# Schematic_Ledtraitim.net
KiCad netlist of a schematic drawn in Altium Designer
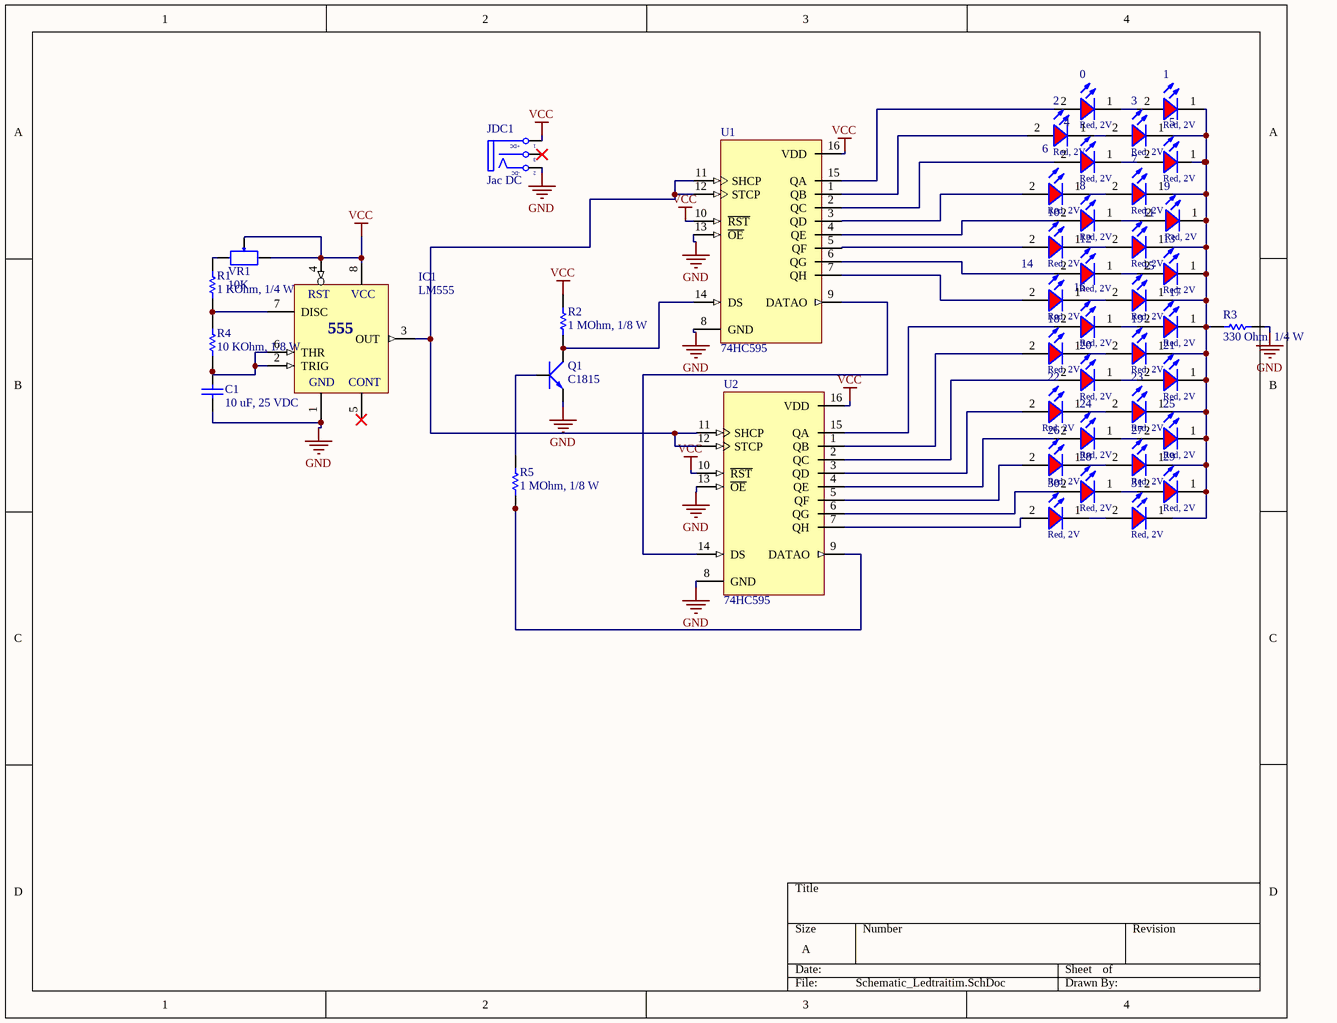
[diagram p0: Schematic_Ledtraitim.SchDoc]

(export (version "E")
  (design (tool "Eeschema 10.0.6"))
  (components
    (comp (ref "0")
      (value "Red, 2V")
      (footprint "WL-SMCW_0805")
      (description "WL-SMCW SMT Mono-color Chip LED Blur, size 0805, Red, 2V, 140deg")
      (libsource (lib "Altium_LED") (part "160805RedBlur"))
    )
    (comp (ref "1")
      (value "Red, 2V")
      (footprint "WL-SMCW_0805")
      (description "WL-SMCW SMT Mono-color Chip LED Blur, size 0805, Red, 2V, 140deg")
      (libsource (lib "Altium_LED") (part "160805RedBlur"))
    )
    (comp (ref "2")
      (value "Red, 2V")
      (footprint "WL-SMCW_0805")
      (description "WL-SMCW SMT Mono-color Chip LED Blur, size 0805, Red, 2V, 140deg")
      (libsource (lib "Altium_LED") (part "160805RedBlur"))
    )
    (comp (ref "3")
      (value "Red, 2V")
      (footprint "WL-SMCW_0805")
      (description "WL-SMCW SMT Mono-color Chip LED Blur, size 0805, Red, 2V, 140deg")
      (libsource (lib "Altium_LED") (part "160805RedBlur"))
    )
    (comp (ref "4")
      (value "Red, 2V")
      (footprint "WL-SMCW_0805")
      (description "WL-SMCW SMT Mono-color Chip LED Blur, size 0805, Red, 2V, 140deg")
      (libsource (lib "Altium_LED") (part "160805RedBlur"))
    )
    (comp (ref "5")
      (value "Red, 2V")
      (footprint "WL-SMCW_0805")
      (description "WL-SMCW SMT Mono-color Chip LED Blur, size 0805, Red, 2V, 140deg")
      (libsource (lib "Altium_LED") (part "160805RedBlur"))
    )
    (comp (ref "6")
      (value "Red, 2V")
      (footprint "WL-SMCW_0805")
      (description "WL-SMCW SMT Mono-color Chip LED Blur, size 0805, Red, 2V, 140deg")
      (libsource (lib "Altium_LED") (part "160805RedBlur"))
    )
    (comp (ref "7")
      (value "Red, 2V")
      (footprint "WL-SMCW_0805")
      (description "WL-SMCW SMT Mono-color Chip LED Blur, size 0805, Red, 2V, 140deg")
      (libsource (lib "Altium_LED") (part "160805RedBlur"))
    )
    (comp (ref "8")
      (value "Red, 2V")
      (footprint "WL-SMCW_0805")
      (description "WL-SMCW SMT Mono-color Chip LED Blur, size 0805, Red, 2V, 140deg")
      (libsource (lib "Altium_LED") (part "160805RedBlur"))
    )
    (comp (ref "9")
      (value "Red, 2V")
      (footprint "WL-SMCW_0805")
      (description "WL-SMCW SMT Mono-color Chip LED Blur, size 0805, Red, 2V, 140deg")
      (libsource (lib "Altium_LED") (part "160805RedBlur"))
    )
    (comp (ref "10")
      (value "Red, 2V")
      (footprint "WL-SMCW_0805")
      (description "WL-SMCW SMT Mono-color Chip LED Blur, size 0805, Red, 2V, 140deg")
      (libsource (lib "Altium_LED") (part "160805RedBlur"))
    )
    (comp (ref "11")
      (value "Red, 2V")
      (footprint "WL-SMCW_0805")
      (description "WL-SMCW SMT Mono-color Chip LED Blur, size 0805, Red, 2V, 140deg")
      (libsource (lib "Altium_LED") (part "160805RedBlur"))
    )
    (comp (ref "12")
      (value "Red, 2V")
      (footprint "WL-SMCW_0805")
      (description "WL-SMCW SMT Mono-color Chip LED Blur, size 0805, Red, 2V, 140deg")
      (libsource (lib "Altium_LED") (part "160805RedBlur"))
    )
    (comp (ref "13")
      (value "Red, 2V")
      (footprint "WL-SMCW_0805")
      (description "WL-SMCW SMT Mono-color Chip LED Blur, size 0805, Red, 2V, 140deg")
      (libsource (lib "Altium_LED") (part "160805RedBlur"))
    )
    (comp (ref "14")
      (value "Red, 2V")
      (footprint "WL-SMCW_0805")
      (description "WL-SMCW SMT Mono-color Chip LED Blur, size 0805, Red, 2V, 140deg")
      (libsource (lib "Altium_LED") (part "160805RedBlur"))
    )
    (comp (ref "15")
      (value "Red, 2V")
      (footprint "WL-SMCW_0805")
      (description "WL-SMCW SMT Mono-color Chip LED Blur, size 0805, Red, 2V, 140deg")
      (libsource (lib "Altium_LED") (part "160805RedBlur"))
    )
    (comp (ref "16")
      (value "Red, 2V")
      (footprint "WL-SMCW_0805")
      (description "WL-SMCW SMT Mono-color Chip LED Blur, size 0805, Red, 2V, 140deg")
      (libsource (lib "Altium_LED") (part "160805RedBlur"))
    )
    (comp (ref "17")
      (value "Red, 2V")
      (footprint "WL-SMCW_0805")
      (description "WL-SMCW SMT Mono-color Chip LED Blur, size 0805, Red, 2V, 140deg")
      (libsource (lib "Altium_LED") (part "160805RedBlur"))
    )
    (comp (ref "18")
      (value "Red, 2V")
      (footprint "WL-SMCW_0805")
      (description "WL-SMCW SMT Mono-color Chip LED Blur, size 0805, Red, 2V, 140deg")
      (libsource (lib "Altium_LED") (part "160805RedBlur"))
    )
    (comp (ref "19")
      (value "Red, 2V")
      (footprint "WL-SMCW_0805")
      (description "WL-SMCW SMT Mono-color Chip LED Blur, size 0805, Red, 2V, 140deg")
      (libsource (lib "Altium_LED") (part "160805RedBlur"))
    )
    (comp (ref "20")
      (value "Red, 2V")
      (footprint "WL-SMCW_0805")
      (description "WL-SMCW SMT Mono-color Chip LED Blur, size 0805, Red, 2V, 140deg")
      (libsource (lib "Altium_LED") (part "160805RedBlur"))
    )
    (comp (ref "21")
      (value "Red, 2V")
      (footprint "WL-SMCW_0805")
      (description "WL-SMCW SMT Mono-color Chip LED Blur, size 0805, Red, 2V, 140deg")
      (libsource (lib "Altium_LED") (part "160805RedBlur"))
    )
    (comp (ref "22")
      (value "Red, 2V")
      (footprint "WL-SMCW_0805")
      (description "WL-SMCW SMT Mono-color Chip LED Blur, size 0805, Red, 2V, 140deg")
      (libsource (lib "Altium_LED") (part "160805RedBlur"))
    )
    (comp (ref "23")
      (value "Red, 2V")
      (footprint "WL-SMCW_0805")
      (description "WL-SMCW SMT Mono-color Chip LED Blur, size 0805, Red, 2V, 140deg")
      (libsource (lib "Altium_LED") (part "160805RedBlur"))
    )
    (comp (ref "24")
      (value "Red, 2V")
      (footprint "WL-SMCW_0805")
      (description "WL-SMCW SMT Mono-color Chip LED Blur, size 0805, Red, 2V, 140deg")
      (libsource (lib "Altium_LED") (part "160805RedBlur"))
    )
    (comp (ref "25")
      (value "Red, 2V")
      (footprint "WL-SMCW_0805")
      (description "WL-SMCW SMT Mono-color Chip LED Blur, size 0805, Red, 2V, 140deg")
      (libsource (lib "Altium_LED") (part "160805RedBlur"))
    )
    (comp (ref "26")
      (value "Red, 2V")
      (footprint "WL-SMCW_0805")
      (description "WL-SMCW SMT Mono-color Chip LED Blur, size 0805, Red, 2V, 140deg")
      (libsource (lib "Altium_LED") (part "160805RedBlur"))
    )
    (comp (ref "27")
      (value "Red, 2V")
      (footprint "WL-SMCW_0805")
      (description "WL-SMCW SMT Mono-color Chip LED Blur, size 0805, Red, 2V, 140deg")
      (libsource (lib "Altium_LED") (part "160805RedBlur"))
    )
    (comp (ref "28")
      (value "Red, 2V")
      (footprint "WL-SMCW_0805")
      (description "WL-SMCW SMT Mono-color Chip LED Blur, size 0805, Red, 2V, 140deg")
      (libsource (lib "Altium_LED") (part "160805RedBlur"))
    )
    (comp (ref "29")
      (value "Red, 2V")
      (footprint "WL-SMCW_0805")
      (description "WL-SMCW SMT Mono-color Chip LED Blur, size 0805, Red, 2V, 140deg")
      (libsource (lib "Altium_LED") (part "160805RedBlur"))
    )
    (comp (ref "30")
      (value "Red, 2V")
      (footprint "WL-SMCW_0805")
      (description "WL-SMCW SMT Mono-color Chip LED Blur, size 0805, Red, 2V, 140deg")
      (libsource (lib "Altium_LED") (part "160805RedBlur"))
    )
    (comp (ref "31")
      (value "Red, 2V")
      (footprint "WL-SMCW_0805")
      (description "WL-SMCW SMT Mono-color Chip LED Blur, size 0805, Red, 2V, 140deg")
      (libsource (lib "Altium_LED") (part "160805RedBlur"))
    )
    (comp (ref "C1")
      (value "10 uF, 25 VDC")
      (footprint "CAP_0805")
      (description "CAP, size 0805, 10 uF, 25 VDC")
      (fields (field (name "TOLERANCE") "+/-10%"))
      (libsource (lib "Altium_Ceramic_Cap") (part "0108051061025"))
    )
    (comp (ref "IC1")
      (value "LM555")
      (footprint "DIP8")
      (description "Timer Circuits")
      (libsource (lib "Cty1") (part "LM555"))
    )
    (comp (ref "JDC1")
      (value "Jac DC")
      (footprint "DC-IN")
      (description "Jac DC input")
      (libsource (lib "Cty1") (part "DCIN"))
    )
    (comp (ref "Q1")
      (value "C1815")
      (footprint "TO126")
      (description "NPN 600mW, ECB")
      (libsource (lib "Devzone_SCHLib") (part "C1815"))
    )
    (comp (ref "R1")
      (value "1 KOhm, 1/4 W")
      (footprint "resistor_0603")
      (description "RES, size 0603, 1 KOhm, 1/4 W")
      (libsource (lib "Altium_Resistor") (part "0006031021"))
    )
    (comp (ref "R2")
      (value "1 MOhm, 1/8 W")
      (footprint "RESISTOR_0805")
      (description "RES, size 0805, 1 MOhm, 1/8 W")
      (libsource (lib "Altium_Resistor") (part "0008051055"))
    )
    (comp (ref "R3")
      (value "330 Ohm, 1/4 W")
      (footprint "resistor_0603")
      (description "RES, size 0603, 330 Ohm, 1/4 W")
      (libsource (lib "Altium_Resistor") (part "0006033311"))
    )
    (comp (ref "R4")
      (value "10 KOhm, 1/8 W")
      (footprint "RESISTOR_0805")
      (description "RES, size 0805, 10 KOhm, 1/8 W")
      (libsource (lib "Altium_Resistor") (part "0008051035"))
    )
    (comp (ref "R5")
      (value "1 MOhm, 1/8 W")
      (footprint "RESISTOR_0805")
      (description "RES, size 0805, 1 MOhm, 1/8 W")
      (libsource (lib "Altium_Resistor") (part "0008051055"))
    )
    (comp (ref "U1")
      (value "74HC595")
      (footprint "DIP16")
      (description "8-Bit Serial-Input/Serial or Prallel-Output Shift Register with Latched 3-State Outputs")
      (fields (field (name "PUBLISHER") "Altium Limited"))
      (libsource (lib "Cty1") (part "74HC595"))
    )
    (comp (ref "U2")
      (value "74HC595")
      (footprint "DIP16")
      (description "8-Bit Serial-Input/Serial or Prallel-Output Shift Register with Latched 3-State Outputs")
      (fields (field (name "PUBLISHER") "Altium Limited"))
      (libsource (lib "Cty1") (part "74HC595"))
    )
    (comp (ref "VR1")
      (value "10K")
      (footprint "VOL_1")
      (description "Var Resistor")
      (libsource (lib "Cty1") (part "Var Resitor"))
    )
  )
  (nets
    (net (code "2") (name "GND") (class "Default")
      (node (ref "C1") (pin "1") (pinfunction "1_1") (pintype "passive"))
      (node (ref "IC1") (pin "1") (pinfunction "GND_1") (pintype "power_in"))
      (node (ref "JDC1") (pin "2") (pinfunction "TN_2") (pintype "passive"))
      (node (ref "Q1") (pin "3") (pinfunction "E_3") (pintype "passive"))
      (node (ref "R3") (pin "2") (pinfunction "2_2") (pintype "passive"))
      (node (ref "U1") (pin "13") (pinfunction "~{OE}_13") (pintype "input"))
      (node (ref "U1") (pin "8") (pinfunction "GND_8") (pintype "power_in"))
      (node (ref "U2") (pin "13") (pinfunction "~{OE}_13") (pintype "input"))
      (node (ref "U2") (pin "8") (pinfunction "GND_8") (pintype "power_in"))
    )
    (net (code "3") (name "Net-(0-A)") (class "Default")
      (node (ref "0") (pin "2") (pinfunction "A_2") (pintype "passive"))
      (node (ref "U1") (pin "15") (pinfunction "QA_15") (pintype "tri_state"))
    )
    (net (code "4") (name "Net-(0-K)") (class "Default")
      (node (ref "0") (pin "1") (pinfunction "K_1") (pintype "passive"))
      (node (ref "1") (pin "2") (pinfunction "A_2") (pintype "passive"))
    )
    (net (code "5") (name "Net-(1-K)") (class "Default")
      (node (ref "1") (pin "1") (pinfunction "K_1") (pintype "passive"))
      (node (ref "11") (pin "1") (pinfunction "K_1") (pintype "passive"))
      (node (ref "13") (pin "1") (pinfunction "K_1") (pintype "passive"))
      (node (ref "15") (pin "1") (pinfunction "K_1") (pintype "passive"))
      (node (ref "17") (pin "1") (pinfunction "K_1") (pintype "passive"))
      (node (ref "19") (pin "1") (pinfunction "K_1") (pintype "passive"))
      (node (ref "21") (pin "1") (pinfunction "K_1") (pintype "passive"))
      (node (ref "23") (pin "1") (pinfunction "K_1") (pintype "passive"))
      (node (ref "25") (pin "1") (pinfunction "K_1") (pintype "passive"))
      (node (ref "27") (pin "1") (pinfunction "K_1") (pintype "passive"))
      (node (ref "29") (pin "1") (pinfunction "K_1") (pintype "passive"))
      (node (ref "3") (pin "1") (pinfunction "K_1") (pintype "passive"))
      (node (ref "31") (pin "1") (pinfunction "K_1") (pintype "passive"))
      (node (ref "5") (pin "1") (pinfunction "K_1") (pintype "passive"))
      (node (ref "7") (pin "1") (pinfunction "K_1") (pintype "passive"))
      (node (ref "9") (pin "1") (pinfunction "K_1") (pintype "passive"))
      (node (ref "R3") (pin "1") (pinfunction "1_1") (pintype "passive"))
    )
    (net (code "6") (name "Net-(2-A)") (class "Default")
      (node (ref "2") (pin "2") (pinfunction "A_2") (pintype "passive"))
      (node (ref "U1") (pin "1") (pinfunction "QB_1") (pintype "tri_state"))
    )
    (net (code "7") (name "Net-(2-K)") (class "Default")
      (node (ref "2") (pin "1") (pinfunction "K_1") (pintype "passive"))
      (node (ref "3") (pin "2") (pinfunction "A_2") (pintype "passive"))
    )
    (net (code "8") (name "Net-(4-A)") (class "Default")
      (node (ref "4") (pin "2") (pinfunction "A_2") (pintype "passive"))
      (node (ref "U1") (pin "2") (pinfunction "QC_2") (pintype "tri_state"))
    )
    (net (code "9") (name "Net-(4-K)") (class "Default")
      (node (ref "4") (pin "1") (pinfunction "K_1") (pintype "passive"))
      (node (ref "5") (pin "2") (pinfunction "A_2") (pintype "passive"))
    )
    (net (code "10") (name "Net-(6-A)") (class "Default")
      (node (ref "6") (pin "2") (pinfunction "A_2") (pintype "passive"))
      (node (ref "U1") (pin "3") (pinfunction "QD_3") (pintype "tri_state"))
    )
    (net (code "11") (name "Net-(6-K)") (class "Default")
      (node (ref "6") (pin "1") (pinfunction "K_1") (pintype "passive"))
      (node (ref "7") (pin "2") (pinfunction "A_2") (pintype "passive"))
    )
    (net (code "12") (name "Net-(8-A)") (class "Default")
      (node (ref "8") (pin "2") (pinfunction "A_2") (pintype "passive"))
      (node (ref "U1") (pin "4") (pinfunction "QE_4") (pintype "tri_state"))
    )
    (net (code "13") (name "Net-(8-K)") (class "Default")
      (node (ref "8") (pin "1") (pinfunction "K_1") (pintype "passive"))
      (node (ref "9") (pin "2") (pinfunction "A_2") (pintype "passive"))
    )
    (net (code "14") (name "Net-(10-A)") (class "Default")
      (node (ref "10") (pin "2") (pinfunction "A_2") (pintype "passive"))
      (node (ref "U1") (pin "5") (pinfunction "QF_5") (pintype "tri_state"))
    )
    (net (code "15") (name "Net-(10-K)") (class "Default")
      (node (ref "10") (pin "1") (pinfunction "K_1") (pintype "passive"))
      (node (ref "11") (pin "2") (pinfunction "A_2") (pintype "passive"))
    )
    (net (code "16") (name "Net-(12-A)") (class "Default")
      (node (ref "12") (pin "2") (pinfunction "A_2") (pintype "passive"))
      (node (ref "U1") (pin "6") (pinfunction "QG_6") (pintype "tri_state"))
    )
    (net (code "17") (name "Net-(12-K)") (class "Default")
      (node (ref "12") (pin "1") (pinfunction "K_1") (pintype "passive"))
      (node (ref "13") (pin "2") (pinfunction "A_2") (pintype "passive"))
    )
    (net (code "18") (name "Net-(14-A)") (class "Default")
      (node (ref "14") (pin "2") (pinfunction "A_2") (pintype "passive"))
      (node (ref "U1") (pin "7") (pinfunction "QH_7") (pintype "tri_state"))
    )
    (net (code "19") (name "Net-(14-K)") (class "Default")
      (node (ref "14") (pin "1") (pinfunction "K_1") (pintype "passive"))
      (node (ref "15") (pin "2") (pinfunction "A_2") (pintype "passive"))
    )
    (net (code "20") (name "Net-(16-A)") (class "Default")
      (node (ref "16") (pin "2") (pinfunction "A_2") (pintype "passive"))
      (node (ref "U2") (pin "15") (pinfunction "QA_15") (pintype "tri_state"))
    )
    (net (code "21") (name "Net-(16-K)") (class "Default")
      (node (ref "16") (pin "1") (pinfunction "K_1") (pintype "passive"))
      (node (ref "17") (pin "2") (pinfunction "A_2") (pintype "passive"))
    )
    (net (code "22") (name "Net-(18-A)") (class "Default")
      (node (ref "18") (pin "2") (pinfunction "A_2") (pintype "passive"))
      (node (ref "U2") (pin "1") (pinfunction "QB_1") (pintype "tri_state"))
    )
    (net (code "23") (name "Net-(18-K)") (class "Default")
      (node (ref "18") (pin "1") (pinfunction "K_1") (pintype "passive"))
      (node (ref "19") (pin "2") (pinfunction "A_2") (pintype "passive"))
    )
    (net (code "24") (name "Net-(20-A)") (class "Default")
      (node (ref "20") (pin "2") (pinfunction "A_2") (pintype "passive"))
      (node (ref "U2") (pin "2") (pinfunction "QC_2") (pintype "tri_state"))
    )
    (net (code "25") (name "Net-(20-K)") (class "Default")
      (node (ref "20") (pin "1") (pinfunction "K_1") (pintype "passive"))
      (node (ref "21") (pin "2") (pinfunction "A_2") (pintype "passive"))
    )
    (net (code "26") (name "Net-(22-A)") (class "Default")
      (node (ref "22") (pin "2") (pinfunction "A_2") (pintype "passive"))
      (node (ref "U2") (pin "3") (pinfunction "QD_3") (pintype "tri_state"))
    )
    (net (code "27") (name "Net-(22-K)") (class "Default")
      (node (ref "22") (pin "1") (pinfunction "K_1") (pintype "passive"))
      (node (ref "23") (pin "2") (pinfunction "A_2") (pintype "passive"))
    )
    (net (code "28") (name "Net-(24-A)") (class "Default")
      (node (ref "24") (pin "2") (pinfunction "A_2") (pintype "passive"))
      (node (ref "U2") (pin "4") (pinfunction "QE_4") (pintype "tri_state"))
    )
    (net (code "29") (name "Net-(24-K)") (class "Default")
      (node (ref "24") (pin "1") (pinfunction "K_1") (pintype "passive"))
      (node (ref "25") (pin "2") (pinfunction "A_2") (pintype "passive"))
    )
    (net (code "30") (name "Net-(26-A)") (class "Default")
      (node (ref "26") (pin "2") (pinfunction "A_2") (pintype "passive"))
      (node (ref "U2") (pin "5") (pinfunction "QF_5") (pintype "tri_state"))
    )
    (net (code "31") (name "Net-(26-K)") (class "Default")
      (node (ref "26") (pin "1") (pinfunction "K_1") (pintype "passive"))
      (node (ref "27") (pin "2") (pinfunction "A_2") (pintype "passive"))
    )
    (net (code "32") (name "Net-(28-A)") (class "Default")
      (node (ref "28") (pin "2") (pinfunction "A_2") (pintype "passive"))
      (node (ref "U2") (pin "6") (pinfunction "QG_6") (pintype "tri_state"))
    )
    (net (code "33") (name "Net-(28-K)") (class "Default")
      (node (ref "28") (pin "1") (pinfunction "K_1") (pintype "passive"))
      (node (ref "29") (pin "2") (pinfunction "A_2") (pintype "passive"))
    )
    (net (code "34") (name "Net-(30-A)") (class "Default")
      (node (ref "30") (pin "2") (pinfunction "A_2") (pintype "passive"))
      (node (ref "U2") (pin "7") (pinfunction "QH_7") (pintype "tri_state"))
    )
    (net (code "35") (name "Net-(30-K)") (class "Default")
      (node (ref "30") (pin "1") (pinfunction "K_1") (pintype "passive"))
      (node (ref "31") (pin "2") (pinfunction "A_2") (pintype "passive"))
    )
    (net (code "36") (name "Net-(IC1-DISC)") (class "Default")
      (node (ref "IC1") (pin "7") (pinfunction "DISC_7") (pintype "open_collector"))
      (node (ref "R1") (pin "1") (pinfunction "1_1") (pintype "passive"))
      (node (ref "R4") (pin "2") (pinfunction "2_2") (pintype "passive"))
    )
    (net (code "37") (name "Net-(IC1-OUT)") (class "Default")
      (node (ref "IC1") (pin "3") (pinfunction "OUT_3") (pintype "output"))
      (node (ref "U1") (pin "11") (pinfunction "SHCP_11") (pintype "input"))
      (node (ref "U1") (pin "12") (pinfunction "STCP_12") (pintype "input"))
      (node (ref "U2") (pin "11") (pinfunction "SHCP_11") (pintype "input"))
      (node (ref "U2") (pin "12") (pinfunction "STCP_12") (pintype "input"))
    )
    (net (code "38") (name "Net-(IC1-THR)") (class "Default")
      (node (ref "C1") (pin "2") (pinfunction "2_2") (pintype "passive"))
      (node (ref "IC1") (pin "2") (pinfunction "TRIG_2") (pintype "input"))
      (node (ref "IC1") (pin "6") (pinfunction "THR_6") (pintype "input"))
      (node (ref "R4") (pin "1") (pinfunction "1_1") (pintype "passive"))
    )
    (net (code "39") (name "Net-(Q1-B)") (class "Default")
      (node (ref "Q1") (pin "1") (pinfunction "B_1") (pintype "passive"))
      (node (ref "R5") (pin "2") (pinfunction "2_2") (pintype "passive"))
    )
    (net (code "40") (name "Net-(Q1-C)") (class "Default")
      (node (ref "Q1") (pin "2") (pinfunction "C_2") (pintype "passive"))
      (node (ref "R2") (pin "1") (pinfunction "1_1") (pintype "passive"))
      (node (ref "U1") (pin "14") (pinfunction "DS_14") (pintype "input"))
    )
    (net (code "41") (name "Net-(R1-Pad2)") (class "Default")
      (node (ref "R1") (pin "2") (pinfunction "2_2") (pintype "passive"))
      (node (ref "VR1") (pin "1") (pinfunction "1_1") (pintype "passive"))
    )
    (net (code "42") (name "Net-(U1-DATAO)") (class "Default")
      (node (ref "U1") (pin "9") (pinfunction "DATAO_9") (pintype "output"))
      (node (ref "U2") (pin "14") (pinfunction "DS_14") (pintype "input"))
    )
    (net (code "43") (name "Net-(U2-DATAO)") (class "Default")
      (node (ref "R5") (pin "1") (pinfunction "1_1") (pintype "passive"))
      (node (ref "U2") (pin "9") (pinfunction "DATAO_9") (pintype "output"))
    )
    (net (code "44") (name "VCC") (class "Default")
      (node (ref "IC1") (pin "4") (pinfunction "RST_4") (pintype "input"))
      (node (ref "IC1") (pin "8") (pinfunction "VCC_8") (pintype "power_in"))
      (node (ref "JDC1") (pin "1") (pinfunction "T_1") (pintype "passive"))
      (node (ref "R2") (pin "2") (pinfunction "2_2") (pintype "passive"))
      (node (ref "U1") (pin "10") (pinfunction "~{RST}_10") (pintype "input"))
      (node (ref "U1") (pin "16") (pinfunction "VDD_16") (pintype "power_in"))
      (node (ref "U2") (pin "10") (pinfunction "~{RST}_10") (pintype "input"))
      (node (ref "U2") (pin "16") (pinfunction "VDD_16") (pintype "power_in"))
      (node (ref "VR1") (pin "2") (pinfunction "2_2") (pintype "passive"))
      (node (ref "VR1") (pin "3") (pinfunction "3_3") (pintype "passive"))
    )
    (net (code "45") (name "unconnected-(IC1-CONT-Pad5)") (class "Default")
      (node (ref "IC1") (pin "5") (pinfunction "CONT_5") (pintype "passive+no_connect"))
    )
    (net (code "46") (name "unconnected-(JDC1-S-Pad3)") (class "Default")
      (node (ref "JDC1") (pin "3") (pinfunction "S_3") (pintype "power_in+no_connect"))
    )
  )
)
